# AmplifierInput.net
KiCad netlist of a schematic drawn in Altium Designer
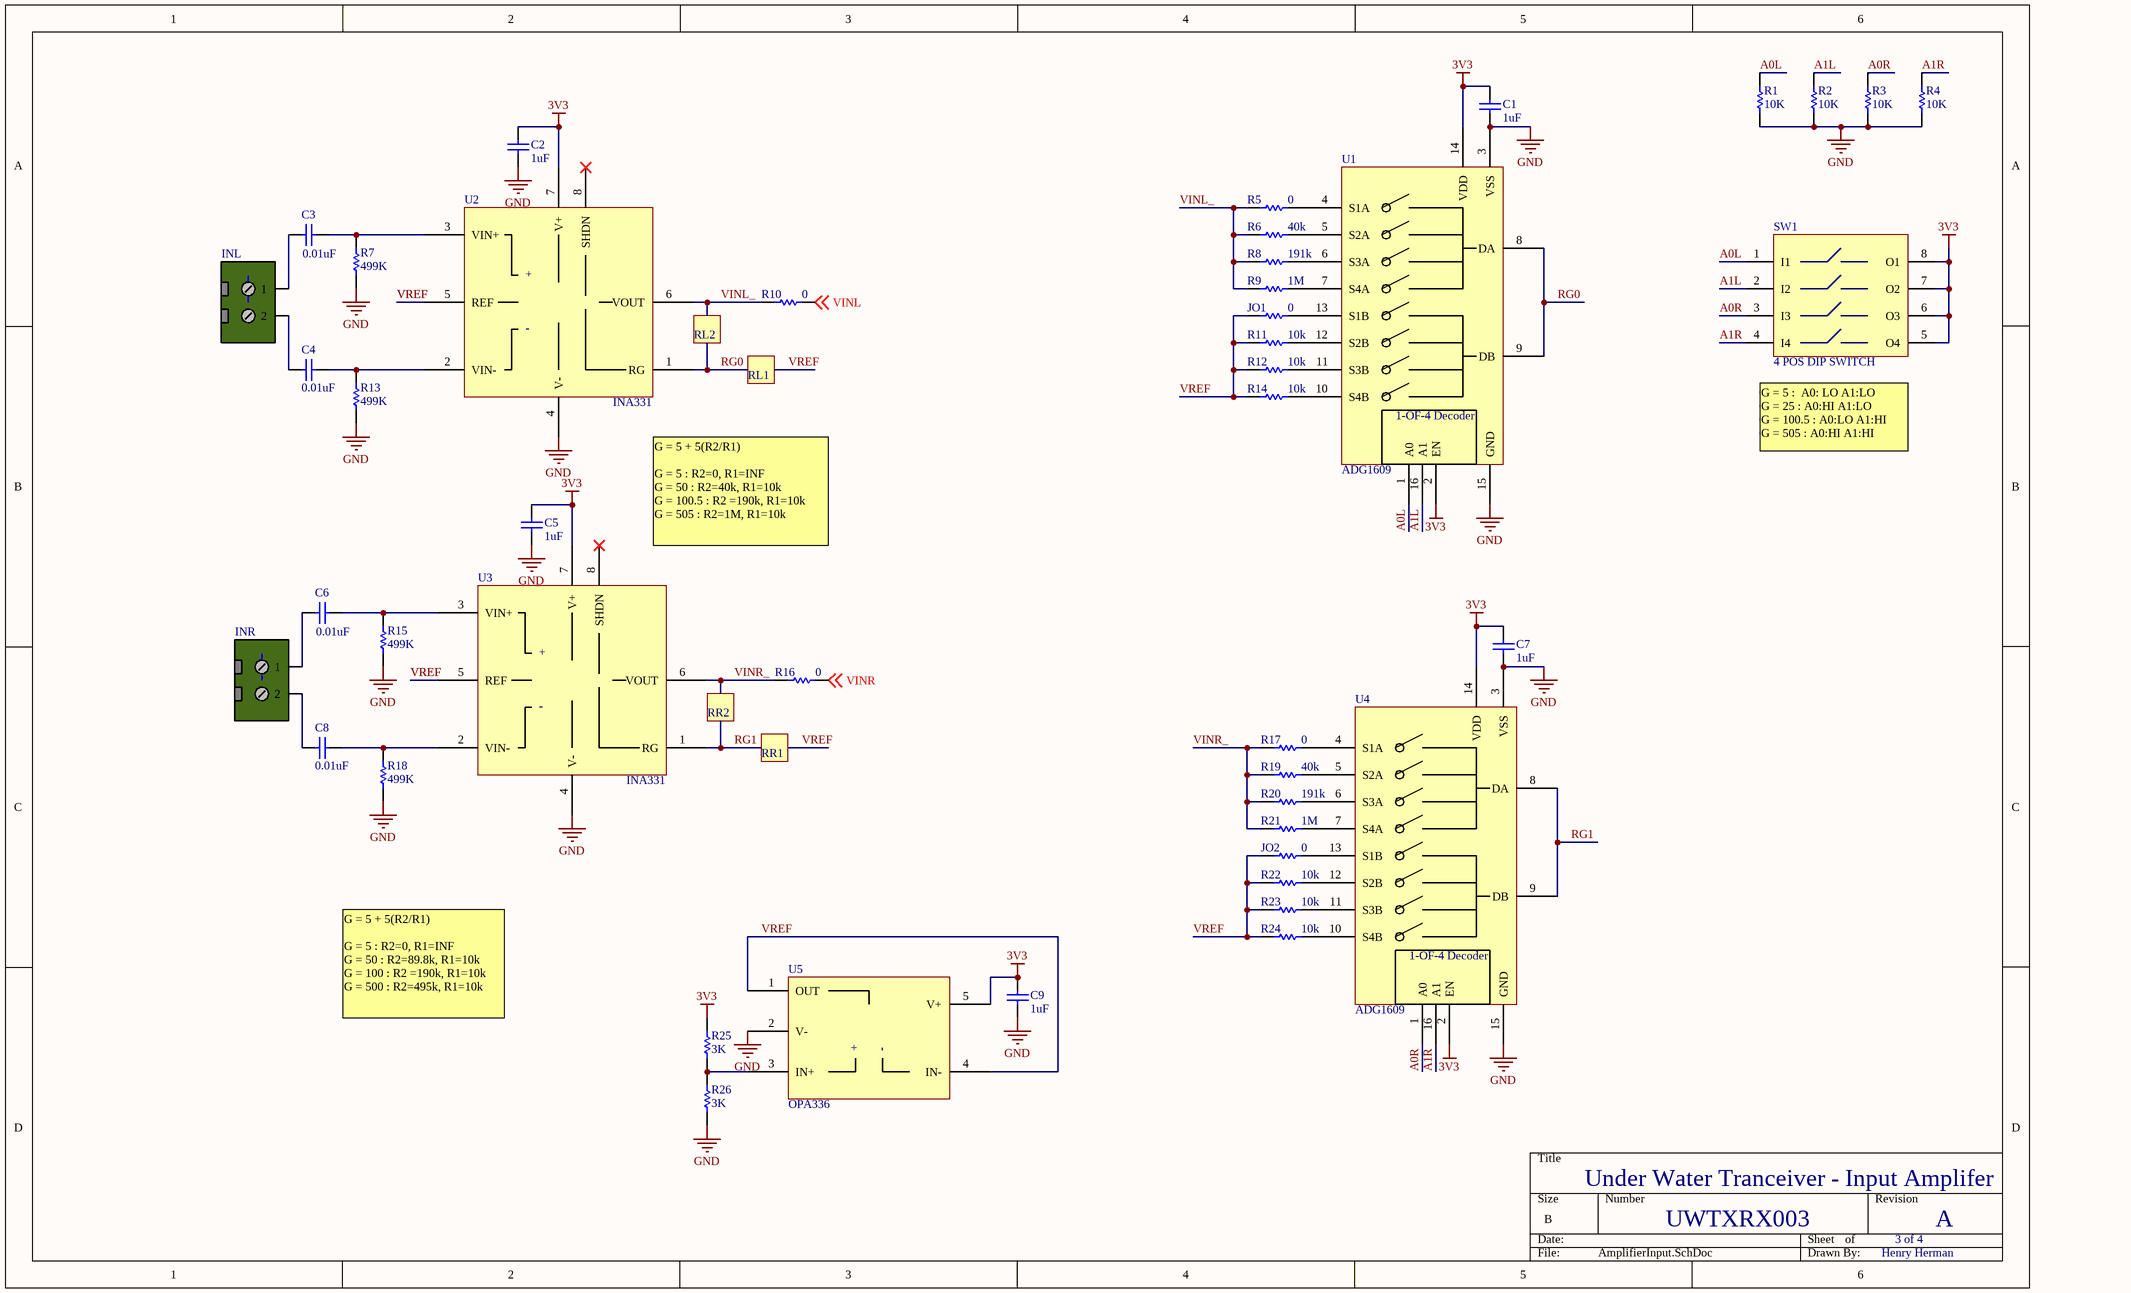
[diagram p0: AmplifierInput.SchDoc]

(export (version "E")
  (design (tool "Eeschema 10.0.6"))
  (components
    (comp (ref "C1")
      (value "1uF")
      (footprint "SM/C_0805")
      (description "CAP")
      (libsource (lib "Henry1_20_2010") (part "CAP"))
    )
    (comp (ref "C2")
      (value "1uF")
      (footprint "SM/C_0805")
      (description "CAP")
      (libsource (lib "Henry1_20_2010") (part "CAP"))
    )
    (comp (ref "C3")
      (value "0.01uF")
      (footprint "SM/C_0805")
      (description "CAP")
      (libsource (lib "Henry1_20_2010") (part "CAP"))
    )
    (comp (ref "C4")
      (value "0.01uF")
      (footprint "SM/C_0805")
      (description "CAP")
      (libsource (lib "Henry1_20_2010") (part "CAP"))
    )
    (comp (ref "C5")
      (value "1uF")
      (footprint "SM/C_0805")
      (description "CAP")
      (libsource (lib "Henry1_20_2010") (part "CAP"))
    )
    (comp (ref "C6")
      (value "0.01uF")
      (footprint "SM/C_0805")
      (description "CAP")
      (libsource (lib "Henry1_20_2010") (part "CAP"))
    )
    (comp (ref "C7")
      (value "1uF")
      (footprint "SM/C_0805")
      (description "CAP")
      (libsource (lib "Henry1_20_2010") (part "CAP"))
    )
    (comp (ref "C8")
      (value "0.01uF")
      (footprint "SM/C_0805")
      (description "CAP")
      (libsource (lib "Henry1_20_2010") (part "CAP"))
    )
    (comp (ref "C9")
      (value "1uF")
      (footprint "SM/C_0805")
      (description "CAP")
      (libsource (lib "Henry1_20_2010") (part "CAP"))
    )
    (comp (ref "INL")
      (value "TERM BLOCK 2POS")
      (footprint "Conn-ScrewTerminal-2pin-Phoenix")
      (libsource (lib "Henry1_20_2010") (part "2Pin-PhoenixTerminalBlock"))
    )
    (comp (ref "INR")
      (value "TERM BLOCK 2POS")
      (footprint "Conn-ScrewTerminal-2pin-Phoenix")
      (libsource (lib "Henry1_20_2010") (part "2Pin-PhoenixTerminalBlock"))
    )
    (comp (ref "JO1")
      (value "0")
      (footprint "SM/R_0805")
      (description "Resistor")
      (fields (field (name "Comment") "Res") (field (name "PUBLISHER") "Altium Limited"))
      (libsource (lib "Henry1_20_2010") (part "Res"))
    )
    (comp (ref "JO2")
      (value "0")
      (footprint "SM/R_0805")
      (description "Resistor")
      (fields (field (name "Comment") "Res") (field (name "PUBLISHER") "Altium Limited"))
      (libsource (lib "Henry1_20_2010") (part "Res"))
    )
    (comp (ref "R1")
      (value "10K")
      (footprint "SM/R_0805")
      (description "Resistor")
      (fields (field (name "Comment") "Res") (field (name "PUBLISHER") "Altium Limited"))
      (libsource (lib "Henry1_20_2010") (part "Res"))
    )
    (comp (ref "R2")
      (value "10K")
      (footprint "SM/R_0805")
      (description "Resistor")
      (fields (field (name "Comment") "Res") (field (name "PUBLISHER") "Altium Limited"))
      (libsource (lib "Henry1_20_2010") (part "Res"))
    )
    (comp (ref "R3")
      (value "10K")
      (footprint "SM/R_0805")
      (description "Resistor")
      (fields (field (name "Comment") "Res") (field (name "PUBLISHER") "Altium Limited"))
      (libsource (lib "Henry1_20_2010") (part "Res"))
    )
    (comp (ref "R4")
      (value "10K")
      (footprint "SM/R_0805")
      (description "Resistor")
      (fields (field (name "Comment") "Res") (field (name "PUBLISHER") "Altium Limited"))
      (libsource (lib "Henry1_20_2010") (part "Res"))
    )
    (comp (ref "R5")
      (value "0")
      (footprint "SM/R_0805")
      (description "Resistor")
      (fields (field (name "Comment") "Res") (field (name "PUBLISHER") "Altium Limited"))
      (libsource (lib "Henry1_20_2010") (part "Res"))
    )
    (comp (ref "R6")
      (value "40k")
      (footprint "SM/R_0805")
      (description "Resistor")
      (fields (field (name "Comment") "Res") (field (name "PUBLISHER") "Altium Limited"))
      (libsource (lib "Henry1_20_2010") (part "Res"))
    )
    (comp (ref "R7")
      (value "499K")
      (footprint "SM/R_0805")
      (description "Resistor")
      (fields (field (name "Comment") "Res") (field (name "PUBLISHER") "Altium Limited"))
      (libsource (lib "Henry1_20_2010") (part "Res"))
    )
    (comp (ref "R8")
      (value "191k")
      (footprint "SM/R_0805")
      (description "Resistor")
      (fields (field (name "Comment") "Res") (field (name "PUBLISHER") "Altium Limited"))
      (libsource (lib "Henry1_20_2010") (part "Res"))
    )
    (comp (ref "R9")
      (value "1M")
      (footprint "SM/R_0805")
      (description "Resistor")
      (fields (field (name "Comment") "Res") (field (name "PUBLISHER") "Altium Limited"))
      (libsource (lib "Henry1_20_2010") (part "Res"))
    )
    (comp (ref "R10")
      (value "0")
      (footprint "SM/R_0805")
      (description "Resistor")
      (fields (field (name "Comment") "Res") (field (name "PUBLISHER") "Altium Limited"))
      (libsource (lib "Henry1_20_2010") (part "Res"))
    )
    (comp (ref "R11")
      (value "10k")
      (footprint "SM/R_0805")
      (description "Resistor")
      (fields (field (name "Comment") "Res") (field (name "PUBLISHER") "Altium Limited"))
      (libsource (lib "Henry1_20_2010") (part "Res"))
    )
    (comp (ref "R12")
      (value "10k")
      (footprint "SM/R_0805")
      (description "Resistor")
      (fields (field (name "Comment") "Res") (field (name "PUBLISHER") "Altium Limited"))
      (libsource (lib "Henry1_20_2010") (part "Res"))
    )
    (comp (ref "R13")
      (value "499K")
      (footprint "SM/R_0805")
      (description "Resistor")
      (fields (field (name "Comment") "Res") (field (name "PUBLISHER") "Altium Limited"))
      (libsource (lib "Henry1_20_2010") (part "Res"))
    )
    (comp (ref "R14")
      (value "10k")
      (footprint "SM/R_0805")
      (description "Resistor")
      (fields (field (name "Comment") "Res") (field (name "PUBLISHER") "Altium Limited"))
      (libsource (lib "Henry1_20_2010") (part "Res"))
    )
    (comp (ref "R15")
      (value "499K")
      (footprint "SM/R_0805")
      (description "Resistor")
      (fields (field (name "Comment") "Res") (field (name "PUBLISHER") "Altium Limited"))
      (libsource (lib "Henry1_20_2010") (part "Res"))
    )
    (comp (ref "R16")
      (value "0")
      (footprint "SM/R_0805")
      (description "Resistor")
      (fields (field (name "Comment") "Res") (field (name "PUBLISHER") "Altium Limited"))
      (libsource (lib "Henry1_20_2010") (part "Res"))
    )
    (comp (ref "R17")
      (value "0")
      (footprint "SM/R_0805")
      (description "Resistor")
      (fields (field (name "Comment") "Res") (field (name "PUBLISHER") "Altium Limited"))
      (libsource (lib "Henry1_20_2010") (part "Res"))
    )
    (comp (ref "R18")
      (value "499K")
      (footprint "SM/R_0805")
      (description "Resistor")
      (fields (field (name "Comment") "Res") (field (name "PUBLISHER") "Altium Limited"))
      (libsource (lib "Henry1_20_2010") (part "Res"))
    )
    (comp (ref "R19")
      (value "40k")
      (footprint "SM/R_0805")
      (description "Resistor")
      (fields (field (name "Comment") "Res") (field (name "PUBLISHER") "Altium Limited"))
      (libsource (lib "Henry1_20_2010") (part "Res"))
    )
    (comp (ref "R20")
      (value "191k")
      (footprint "SM/R_0805")
      (description "Resistor")
      (fields (field (name "Comment") "Res") (field (name "PUBLISHER") "Altium Limited"))
      (libsource (lib "Henry1_20_2010") (part "Res"))
    )
    (comp (ref "R21")
      (value "1M")
      (footprint "SM/R_0805")
      (description "Resistor")
      (fields (field (name "Comment") "Res") (field (name "PUBLISHER") "Altium Limited"))
      (libsource (lib "Henry1_20_2010") (part "Res"))
    )
    (comp (ref "R22")
      (value "10k")
      (footprint "SM/R_0805")
      (description "Resistor")
      (fields (field (name "Comment") "Res") (field (name "PUBLISHER") "Altium Limited"))
      (libsource (lib "Henry1_20_2010") (part "Res"))
    )
    (comp (ref "R23")
      (value "10k")
      (footprint "SM/R_0805")
      (description "Resistor")
      (fields (field (name "Comment") "Res") (field (name "PUBLISHER") "Altium Limited"))
      (libsource (lib "Henry1_20_2010") (part "Res"))
    )
    (comp (ref "R24")
      (value "10k")
      (footprint "SM/R_0805")
      (description "Resistor")
      (fields (field (name "Comment") "Res") (field (name "PUBLISHER") "Altium Limited"))
      (libsource (lib "Henry1_20_2010") (part "Res"))
    )
    (comp (ref "R25")
      (value "3K")
      (footprint "SM/R_0805")
      (description "Resistor")
      (fields (field (name "Comment") "Res") (field (name "PUBLISHER") "Altium Limited"))
      (libsource (lib "Henry1_20_2010") (part "Res"))
    )
    (comp (ref "R26")
      (value "3K")
      (footprint "SM/R_0805")
      (description "Resistor")
      (fields (field (name "Comment") "Res") (field (name "PUBLISHER") "Altium Limited"))
      (libsource (lib "Henry1_20_2010") (part "Res"))
    )
    (comp (ref "SW1")
      (value "4 POS DIP SWITCH")
      (footprint "DIPSW4PIN")
      (libsource (lib "Henry1_20_2010") (part "4 POS DIP SWITCH"))
    )
    (comp (ref "U1")
      (value "ADG1609")
      (footprint "TSSOP 16LEAD - Analog Devices - ADG1609")
      (libsource (lib "Henry1_20_2010") (part "ADG1609"))
    )
    (comp (ref "U2")
      (value "INA331")
      (footprint "MSOP-8PIN-TI")
      (libsource (lib "Henry1_20_2010") (part "INA331"))
    )
    (comp (ref "U3")
      (value "INA331")
      (footprint "MSOP-8PIN-TI")
      (libsource (lib "Henry1_20_2010") (part "INA331"))
    )
    (comp (ref "U4")
      (value "ADG1609")
      (footprint "TSSOP 16LEAD - Analog Devices - ADG1609")
      (libsource (lib "Henry1_20_2010") (part "ADG1609"))
    )
    (comp (ref "U5")
      (value "OPA336")
      (footprint "SOT23-5 -TI")
      (libsource (lib "Henry1_20_2010") (part "OPA335"))
    )
  )
  (nets
    (net (code "1") (name "/A0L") (class "Default")
      (node (ref "R1") (pin "2") (pinfunction "2_2") (pintype "passive"))
      (node (ref "SW1") (pin "1") (pinfunction "I1_1") (pintype "passive"))
      (node (ref "U1") (pin "1") (pinfunction "A0_1") (pintype "passive"))
    )
    (net (code "2") (name "/A0R") (class "Default")
      (node (ref "R3") (pin "2") (pinfunction "2_2") (pintype "passive"))
      (node (ref "SW1") (pin "3") (pinfunction "I3_3") (pintype "passive"))
      (node (ref "U4") (pin "1") (pinfunction "A0_1") (pintype "passive"))
    )
    (net (code "3") (name "/A1L") (class "Default")
      (node (ref "R2") (pin "2") (pinfunction "2_2") (pintype "passive"))
      (node (ref "SW1") (pin "2") (pinfunction "I2_2") (pintype "passive"))
      (node (ref "U1") (pin "16") (pinfunction "A1_16") (pintype "passive"))
    )
    (net (code "4") (name "/A1R") (class "Default")
      (node (ref "R4") (pin "2") (pinfunction "2_2") (pintype "passive"))
      (node (ref "SW1") (pin "4") (pinfunction "I4_4") (pintype "passive"))
      (node (ref "U4") (pin "16") (pinfunction "A1_16") (pintype "passive"))
    )
    (net (code "5") (name "/RG0") (class "Default")
      (node (ref "U1") (pin "8") (pinfunction "DA_8") (pintype "passive"))
      (node (ref "U1") (pin "9") (pinfunction "DB_9") (pintype "passive"))
      (node (ref "U2") (pin "1") (pinfunction "RG_1") (pintype "passive"))
    )
    (net (code "6") (name "/RG1") (class "Default")
      (node (ref "U3") (pin "1") (pinfunction "RG_1") (pintype "passive"))
      (node (ref "U4") (pin "8") (pinfunction "DA_8") (pintype "passive"))
      (node (ref "U4") (pin "9") (pinfunction "DB_9") (pintype "passive"))
    )
    (net (code "7") (name "/VINL_") (class "Default")
      (node (ref "R10") (pin "2") (pinfunction "2_2") (pintype "passive"))
      (node (ref "R5") (pin "2") (pinfunction "2_2") (pintype "passive"))
      (node (ref "R6") (pin "2") (pinfunction "2_2") (pintype "passive"))
      (node (ref "R8") (pin "2") (pinfunction "2_2") (pintype "passive"))
      (node (ref "R9") (pin "2") (pinfunction "2_2") (pintype "passive"))
      (node (ref "U2") (pin "6") (pinfunction "VOUT_6") (pintype "passive"))
    )
    (net (code "8") (name "/VINR_") (class "Default")
      (node (ref "R16") (pin "2") (pinfunction "2_2") (pintype "passive"))
      (node (ref "R17") (pin "2") (pinfunction "2_2") (pintype "passive"))
      (node (ref "R19") (pin "2") (pinfunction "2_2") (pintype "passive"))
      (node (ref "R20") (pin "2") (pinfunction "2_2") (pintype "passive"))
      (node (ref "R21") (pin "2") (pinfunction "2_2") (pintype "passive"))
      (node (ref "U3") (pin "6") (pinfunction "VOUT_6") (pintype "passive"))
    )
    (net (code "9") (name "/VREF") (class "Default")
      (node (ref "JO1") (pin "2") (pinfunction "2_2") (pintype "passive"))
      (node (ref "JO2") (pin "2") (pinfunction "2_2") (pintype "passive"))
      (node (ref "R11") (pin "2") (pinfunction "2_2") (pintype "passive"))
      (node (ref "R12") (pin "2") (pinfunction "2_2") (pintype "passive"))
      (node (ref "R14") (pin "2") (pinfunction "2_2") (pintype "passive"))
      (node (ref "R22") (pin "2") (pinfunction "2_2") (pintype "passive"))
      (node (ref "R23") (pin "2") (pinfunction "2_2") (pintype "passive"))
      (node (ref "R24") (pin "2") (pinfunction "2_2") (pintype "passive"))
      (node (ref "U2") (pin "5") (pinfunction "REF_5") (pintype "passive"))
      (node (ref "U3") (pin "5") (pinfunction "REF_5") (pintype "passive"))
      (node (ref "U5") (pin "1") (pinfunction "OUT_1") (pintype "passive"))
      (node (ref "U5") (pin "4") (pinfunction "IN-_4") (pintype "passive"))
    )
    (net (code "10") (name "3V3") (class "Default")
      (node (ref "C1") (pin "1") (pinfunction "1_1") (pintype "passive"))
      (node (ref "C2") (pin "1") (pinfunction "1_1") (pintype "passive"))
      (node (ref "C5") (pin "1") (pinfunction "1_1") (pintype "passive"))
      (node (ref "C7") (pin "1") (pinfunction "1_1") (pintype "passive"))
      (node (ref "C9") (pin "1") (pinfunction "1_1") (pintype "passive"))
      (node (ref "R25") (pin "1") (pinfunction "1_1") (pintype "passive"))
      (node (ref "SW1") (pin "5") (pinfunction "O4_5") (pintype "passive"))
      (node (ref "SW1") (pin "6") (pinfunction "O3_6") (pintype "passive"))
      (node (ref "SW1") (pin "7") (pinfunction "O2_7") (pintype "passive"))
      (node (ref "SW1") (pin "8") (pinfunction "O1_8") (pintype "passive"))
      (node (ref "U1") (pin "14") (pinfunction "VDD_14") (pintype "passive"))
      (node (ref "U1") (pin "2") (pinfunction "EN_2") (pintype "passive"))
      (node (ref "U2") (pin "7") (pinfunction "V+_7") (pintype "passive"))
      (node (ref "U3") (pin "7") (pinfunction "V+_7") (pintype "passive"))
      (node (ref "U4") (pin "14") (pinfunction "VDD_14") (pintype "passive"))
      (node (ref "U4") (pin "2") (pinfunction "EN_2") (pintype "passive"))
      (node (ref "U5") (pin "5") (pinfunction "V+_5") (pintype "passive"))
    )
    (net (code "11") (name "GND") (class "Default")
      (node (ref "C1") (pin "2") (pinfunction "2_2") (pintype "passive"))
      (node (ref "C2") (pin "2") (pinfunction "2_2") (pintype "passive"))
      (node (ref "C5") (pin "2") (pinfunction "2_2") (pintype "passive"))
      (node (ref "C7") (pin "2") (pinfunction "2_2") (pintype "passive"))
      (node (ref "C9") (pin "2") (pinfunction "2_2") (pintype "passive"))
      (node (ref "R1") (pin "1") (pinfunction "1_1") (pintype "passive"))
      (node (ref "R13") (pin "2") (pinfunction "2_2") (pintype "passive"))
      (node (ref "R15") (pin "2") (pinfunction "2_2") (pintype "passive"))
      (node (ref "R18") (pin "2") (pinfunction "2_2") (pintype "passive"))
      (node (ref "R2") (pin "1") (pinfunction "1_1") (pintype "passive"))
      (node (ref "R26") (pin "2") (pinfunction "2_2") (pintype "passive"))
      (node (ref "R3") (pin "1") (pinfunction "1_1") (pintype "passive"))
      (node (ref "R4") (pin "1") (pinfunction "1_1") (pintype "passive"))
      (node (ref "R7") (pin "2") (pinfunction "2_2") (pintype "passive"))
      (node (ref "U1") (pin "15") (pinfunction "GND_15") (pintype "passive"))
      (node (ref "U1") (pin "3") (pinfunction "VSS_3") (pintype "passive"))
      (node (ref "U2") (pin "4") (pinfunction "V-_4") (pintype "passive"))
      (node (ref "U3") (pin "4") (pinfunction "V-_4") (pintype "passive"))
      (node (ref "U4") (pin "15") (pinfunction "GND_15") (pintype "passive"))
      (node (ref "U4") (pin "3") (pinfunction "VSS_3") (pintype "passive"))
      (node (ref "U5") (pin "2") (pinfunction "V-_2") (pintype "passive"))
    )
    (net (code "12") (name "Net-(C3-Pad2)") (class "Default")
      (node (ref "C3") (pin "2") (pinfunction "2_2") (pintype "passive"))
      (node (ref "INL") (pin "1") (pinfunction "1_1") (pintype "passive"))
    )
    (net (code "13") (name "Net-(C4-Pad2)") (class "Default")
      (node (ref "C4") (pin "2") (pinfunction "2_2") (pintype "passive"))
      (node (ref "INL") (pin "2") (pinfunction "2_2") (pintype "passive"))
    )
    (net (code "14") (name "Net-(C6-Pad2)") (class "Default")
      (node (ref "C6") (pin "2") (pinfunction "2_2") (pintype "passive"))
      (node (ref "INR") (pin "1") (pinfunction "1_1") (pintype "passive"))
    )
    (net (code "15") (name "Net-(C8-Pad2)") (class "Default")
      (node (ref "C8") (pin "2") (pinfunction "2_2") (pintype "passive"))
      (node (ref "INR") (pin "2") (pinfunction "2_2") (pintype "passive"))
    )
    (net (code "16") (name "Net-(U1-S1A)") (class "Default")
      (node (ref "R5") (pin "1") (pinfunction "1_1") (pintype "passive"))
      (node (ref "U1") (pin "4") (pinfunction "S1A_4") (pintype "passive"))
    )
    (net (code "17") (name "Net-(U1-S1B)") (class "Default")
      (node (ref "JO1") (pin "1") (pinfunction "1_1") (pintype "passive"))
      (node (ref "U1") (pin "13") (pinfunction "S1B_13") (pintype "passive"))
    )
    (net (code "18") (name "Net-(U1-S2A)") (class "Default")
      (node (ref "R6") (pin "1") (pinfunction "1_1") (pintype "passive"))
      (node (ref "U1") (pin "5") (pinfunction "S2A_5") (pintype "passive"))
    )
    (net (code "19") (name "Net-(U1-S2B)") (class "Default")
      (node (ref "R11") (pin "1") (pinfunction "1_1") (pintype "passive"))
      (node (ref "U1") (pin "12") (pinfunction "S2B_12") (pintype "passive"))
    )
    (net (code "20") (name "Net-(U1-S3A)") (class "Default")
      (node (ref "R8") (pin "1") (pinfunction "1_1") (pintype "passive"))
      (node (ref "U1") (pin "6") (pinfunction "S3A_6") (pintype "passive"))
    )
    (net (code "21") (name "Net-(U1-S3B)") (class "Default")
      (node (ref "R12") (pin "1") (pinfunction "1_1") (pintype "passive"))
      (node (ref "U1") (pin "11") (pinfunction "S3B_11") (pintype "passive"))
    )
    (net (code "22") (name "Net-(U1-S4A)") (class "Default")
      (node (ref "R9") (pin "1") (pinfunction "1_1") (pintype "passive"))
      (node (ref "U1") (pin "7") (pinfunction "S4A_7") (pintype "passive"))
    )
    (net (code "23") (name "Net-(U1-S4B)") (class "Default")
      (node (ref "R14") (pin "1") (pinfunction "1_1") (pintype "passive"))
      (node (ref "U1") (pin "10") (pinfunction "S4B_10") (pintype "passive"))
    )
    (net (code "24") (name "Net-(U2-VIN+)") (class "Default")
      (node (ref "C3") (pin "1") (pinfunction "1_1") (pintype "passive"))
      (node (ref "R7") (pin "1") (pinfunction "1_1") (pintype "passive"))
      (node (ref "U2") (pin "3") (pinfunction "VIN+_3") (pintype "passive"))
    )
    (net (code "25") (name "Net-(U2-VIN-)") (class "Default")
      (node (ref "C4") (pin "1") (pinfunction "1_1") (pintype "passive"))
      (node (ref "R13") (pin "1") (pinfunction "1_1") (pintype "passive"))
      (node (ref "U2") (pin "2") (pinfunction "VIN-_2") (pintype "passive"))
    )
    (net (code "26") (name "Net-(U3-VIN+)") (class "Default")
      (node (ref "C6") (pin "1") (pinfunction "1_1") (pintype "passive"))
      (node (ref "R15") (pin "1") (pinfunction "1_1") (pintype "passive"))
      (node (ref "U3") (pin "3") (pinfunction "VIN+_3") (pintype "passive"))
    )
    (net (code "27") (name "Net-(U3-VIN-)") (class "Default")
      (node (ref "C8") (pin "1") (pinfunction "1_1") (pintype "passive"))
      (node (ref "R18") (pin "1") (pinfunction "1_1") (pintype "passive"))
      (node (ref "U3") (pin "2") (pinfunction "VIN-_2") (pintype "passive"))
    )
    (net (code "28") (name "Net-(U4-S1A)") (class "Default")
      (node (ref "R17") (pin "1") (pinfunction "1_1") (pintype "passive"))
      (node (ref "U4") (pin "4") (pinfunction "S1A_4") (pintype "passive"))
    )
    (net (code "29") (name "Net-(U4-S1B)") (class "Default")
      (node (ref "JO2") (pin "1") (pinfunction "1_1") (pintype "passive"))
      (node (ref "U4") (pin "13") (pinfunction "S1B_13") (pintype "passive"))
    )
    (net (code "30") (name "Net-(U4-S2A)") (class "Default")
      (node (ref "R19") (pin "1") (pinfunction "1_1") (pintype "passive"))
      (node (ref "U4") (pin "5") (pinfunction "S2A_5") (pintype "passive"))
    )
    (net (code "31") (name "Net-(U4-S2B)") (class "Default")
      (node (ref "R22") (pin "1") (pinfunction "1_1") (pintype "passive"))
      (node (ref "U4") (pin "12") (pinfunction "S2B_12") (pintype "passive"))
    )
    (net (code "32") (name "Net-(U4-S3A)") (class "Default")
      (node (ref "R20") (pin "1") (pinfunction "1_1") (pintype "passive"))
      (node (ref "U4") (pin "6") (pinfunction "S3A_6") (pintype "passive"))
    )
    (net (code "33") (name "Net-(U4-S3B)") (class "Default")
      (node (ref "R23") (pin "1") (pinfunction "1_1") (pintype "passive"))
      (node (ref "U4") (pin "11") (pinfunction "S3B_11") (pintype "passive"))
    )
    (net (code "34") (name "Net-(U4-S4A)") (class "Default")
      (node (ref "R21") (pin "1") (pinfunction "1_1") (pintype "passive"))
      (node (ref "U4") (pin "7") (pinfunction "S4A_7") (pintype "passive"))
    )
    (net (code "35") (name "Net-(U4-S4B)") (class "Default")
      (node (ref "R24") (pin "1") (pinfunction "1_1") (pintype "passive"))
      (node (ref "U4") (pin "10") (pinfunction "S4B_10") (pintype "passive"))
    )
    (net (code "36") (name "Net-(U5-IN+)") (class "Default")
      (node (ref "R25") (pin "2") (pinfunction "2_2") (pintype "passive"))
      (node (ref "R26") (pin "1") (pinfunction "1_1") (pintype "passive"))
      (node (ref "U5") (pin "3") (pinfunction "IN+_3") (pintype "passive"))
    )
    (net (code "37") (name "VINL") (class "Default")
      (node (ref "R10") (pin "1") (pinfunction "1_1") (pintype "passive"))
    )
    (net (code "38") (name "VINR") (class "Default")
      (node (ref "R16") (pin "1") (pinfunction "1_1") (pintype "passive"))
    )
    (net (code "39") (name "unconnected-(U2-SHDN-Pad8)") (class "Default")
      (node (ref "U2") (pin "8") (pinfunction "SHDN_8") (pintype "passive+no_connect"))
    )
    (net (code "40") (name "unconnected-(U3-SHDN-Pad8)") (class "Default")
      (node (ref "U3") (pin "8") (pinfunction "SHDN_8") (pintype "passive+no_connect"))
    )
  )
)
